# LED_Buzzer.net
KiCad netlist of a schematic drawn in Altium Designer
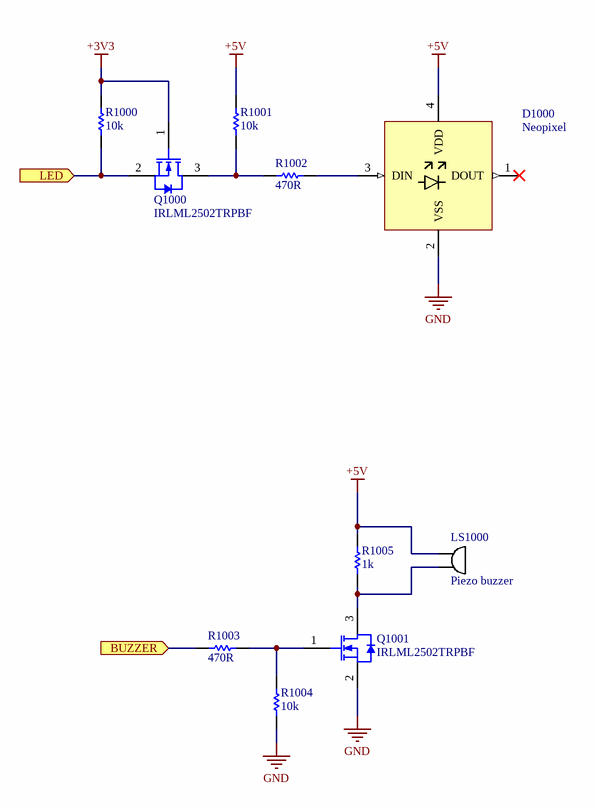
[diagram p0: LED_Buzzer.SchDoc]

(export (version "E")
  (design (tool "Eeschema 10.0.6"))
  (components
    (comp (ref "D1000")
      (value "Neopixel")
      (footprint "2659")
      (description "Adafruit Neopixel SMD 3535\r\nAdafruit part no. 2659\r\nDigikey part no. 1528-1542-ND")
      (fields (field (name "MP") "2659") (field (name "MF") "Adafruit Industries"))
      (libsource (lib "Moonlight_Components") (part "Neopixel"))
    )
    (comp (ref "LS1000")
      (value "Piezo buzzer")
      (footprint "CPT-9019S-SMT-TR")
      (description "4kHz 65 dB @ 3V passive piezoelectric buzzer")
      (libsource (lib "Moonlight_Components") (part "Buzzer"))
    )
    (comp (ref "Q1000")
      (value "IRLML2502TRPBF")
      (footprint "INTR-SOT-23-3_V")
      (description "N-Channel HEXFET(R) Power MOSFET, 20 V VDS, +/- 12 V VGS, 4.2 A, 3-Pin SOT23, RoHS, Tape and Reel")
      (fields (field (name "MANUFACTURER") "International Rectifier"))
      (libsource (lib "Moonlight_Components") (part "IRLML2502TRPBF"))
    )
    (comp (ref "Q1001")
      (value "IRLML2502TRPBF")
      (footprint "INTR-SOT-23-3_V")
      (description "N-Channel HEXFET(R) Power MOSFET, 20 V VDS, +/- 12 V VGS, 4.2 A, 3-Pin SOT23, RoHS, Tape and Reel")
      (fields (field (name "MANUFACTURER") "International Rectifier"))
      (libsource (lib "Moonlight_Components") (part "IRLML2502TRPBF"))
    )
    (comp (ref "R1000")
      (value "10k")
      (footprint "0603_RES")
      (libsource (lib "Moonlight_Components") (part "Resistor"))
    )
    (comp (ref "R1001")
      (value "10k")
      (footprint "0603_RES")
      (libsource (lib "Moonlight_Components") (part "Resistor"))
    )
    (comp (ref "R1002")
      (value "470R")
      (footprint "0603_RES")
      (libsource (lib "Moonlight_Components") (part "Resistor"))
    )
    (comp (ref "R1003")
      (value "470R")
      (footprint "0603_RES")
      (libsource (lib "Moonlight_Components") (part "Resistor"))
    )
    (comp (ref "R1004")
      (value "10k")
      (footprint "0603_RES")
      (libsource (lib "Moonlight_Components") (part "Resistor"))
    )
    (comp (ref "R1005")
      (value "1k")
      (footprint "0603_RES")
      (libsource (lib "Moonlight_Components") (part "Resistor"))
    )
  )
  (nets
    (net (code "1") (name "+3V3") (class "Default")
      (node (ref "Q1000") (pin "1") (pinfunction "G_1") (pintype "passive"))
      (node (ref "R1000") (pin "2") (pinfunction "2_2") (pintype "passive"))
    )
    (net (code "2") (name "+5V") (class "Default")
      (node (ref "D1000") (pin "4") (pinfunction "VDD_4") (pintype "power_in"))
      (node (ref "LS1000") (pin "1") (pintype "passive"))
      (node (ref "R1001") (pin "1") (pinfunction "1_1") (pintype "passive"))
      (node (ref "R1005") (pin "1") (pinfunction "1_1") (pintype "passive"))
    )
    (net (code "3") (name "/BUZZER") (class "Default")
      (node (ref "R1003") (pin "1") (pinfunction "1_1") (pintype "passive"))
    )
    (net (code "4") (name "/LED") (class "Default")
      (node (ref "Q1000") (pin "2") (pinfunction "S_2") (pintype "passive"))
      (node (ref "R1000") (pin "1") (pinfunction "1_1") (pintype "passive"))
    )
    (net (code "5") (name "GND") (class "Default")
      (node (ref "D1000") (pin "2") (pinfunction "VSS_2") (pintype "power_in"))
      (node (ref "Q1001") (pin "2") (pinfunction "S_2") (pintype "passive"))
      (node (ref "R1004") (pin "1") (pinfunction "1_1") (pintype "passive"))
    )
    (net (code "6") (name "Net-(D1000-DIN)") (class "Default")
      (node (ref "D1000") (pin "3") (pinfunction "DIN_3") (pintype "input"))
      (node (ref "R1002") (pin "2") (pinfunction "2_2") (pintype "passive"))
    )
    (net (code "7") (name "Net-(Q1000-D)") (class "Default")
      (node (ref "Q1000") (pin "3") (pinfunction "D_3") (pintype "passive"))
      (node (ref "R1001") (pin "2") (pinfunction "2_2") (pintype "passive"))
      (node (ref "R1002") (pin "1") (pinfunction "1_1") (pintype "passive"))
    )
    (net (code "8") (name "Net-(Q1001-D)") (class "Default")
      (node (ref "LS1000") (pin "2") (pintype "passive"))
      (node (ref "Q1001") (pin "3") (pinfunction "D_3") (pintype "passive"))
      (node (ref "R1005") (pin "2") (pinfunction "2_2") (pintype "passive"))
    )
    (net (code "9") (name "Net-(Q1001-G)") (class "Default")
      (node (ref "Q1001") (pin "1") (pinfunction "G_1") (pintype "passive"))
      (node (ref "R1003") (pin "2") (pinfunction "2_2") (pintype "passive"))
      (node (ref "R1004") (pin "2") (pinfunction "2_2") (pintype "passive"))
    )
    (net (code "10") (name "unconnected-(D1000-DOUT-Pad1)") (class "Default")
      (node (ref "D1000") (pin "1") (pinfunction "DOUT_1") (pintype "output+no_connect"))
    )
  )
)
